# Enclosure_85x58_BHWSL.net
KiCad netlist of a schematic drawn in EAGLE
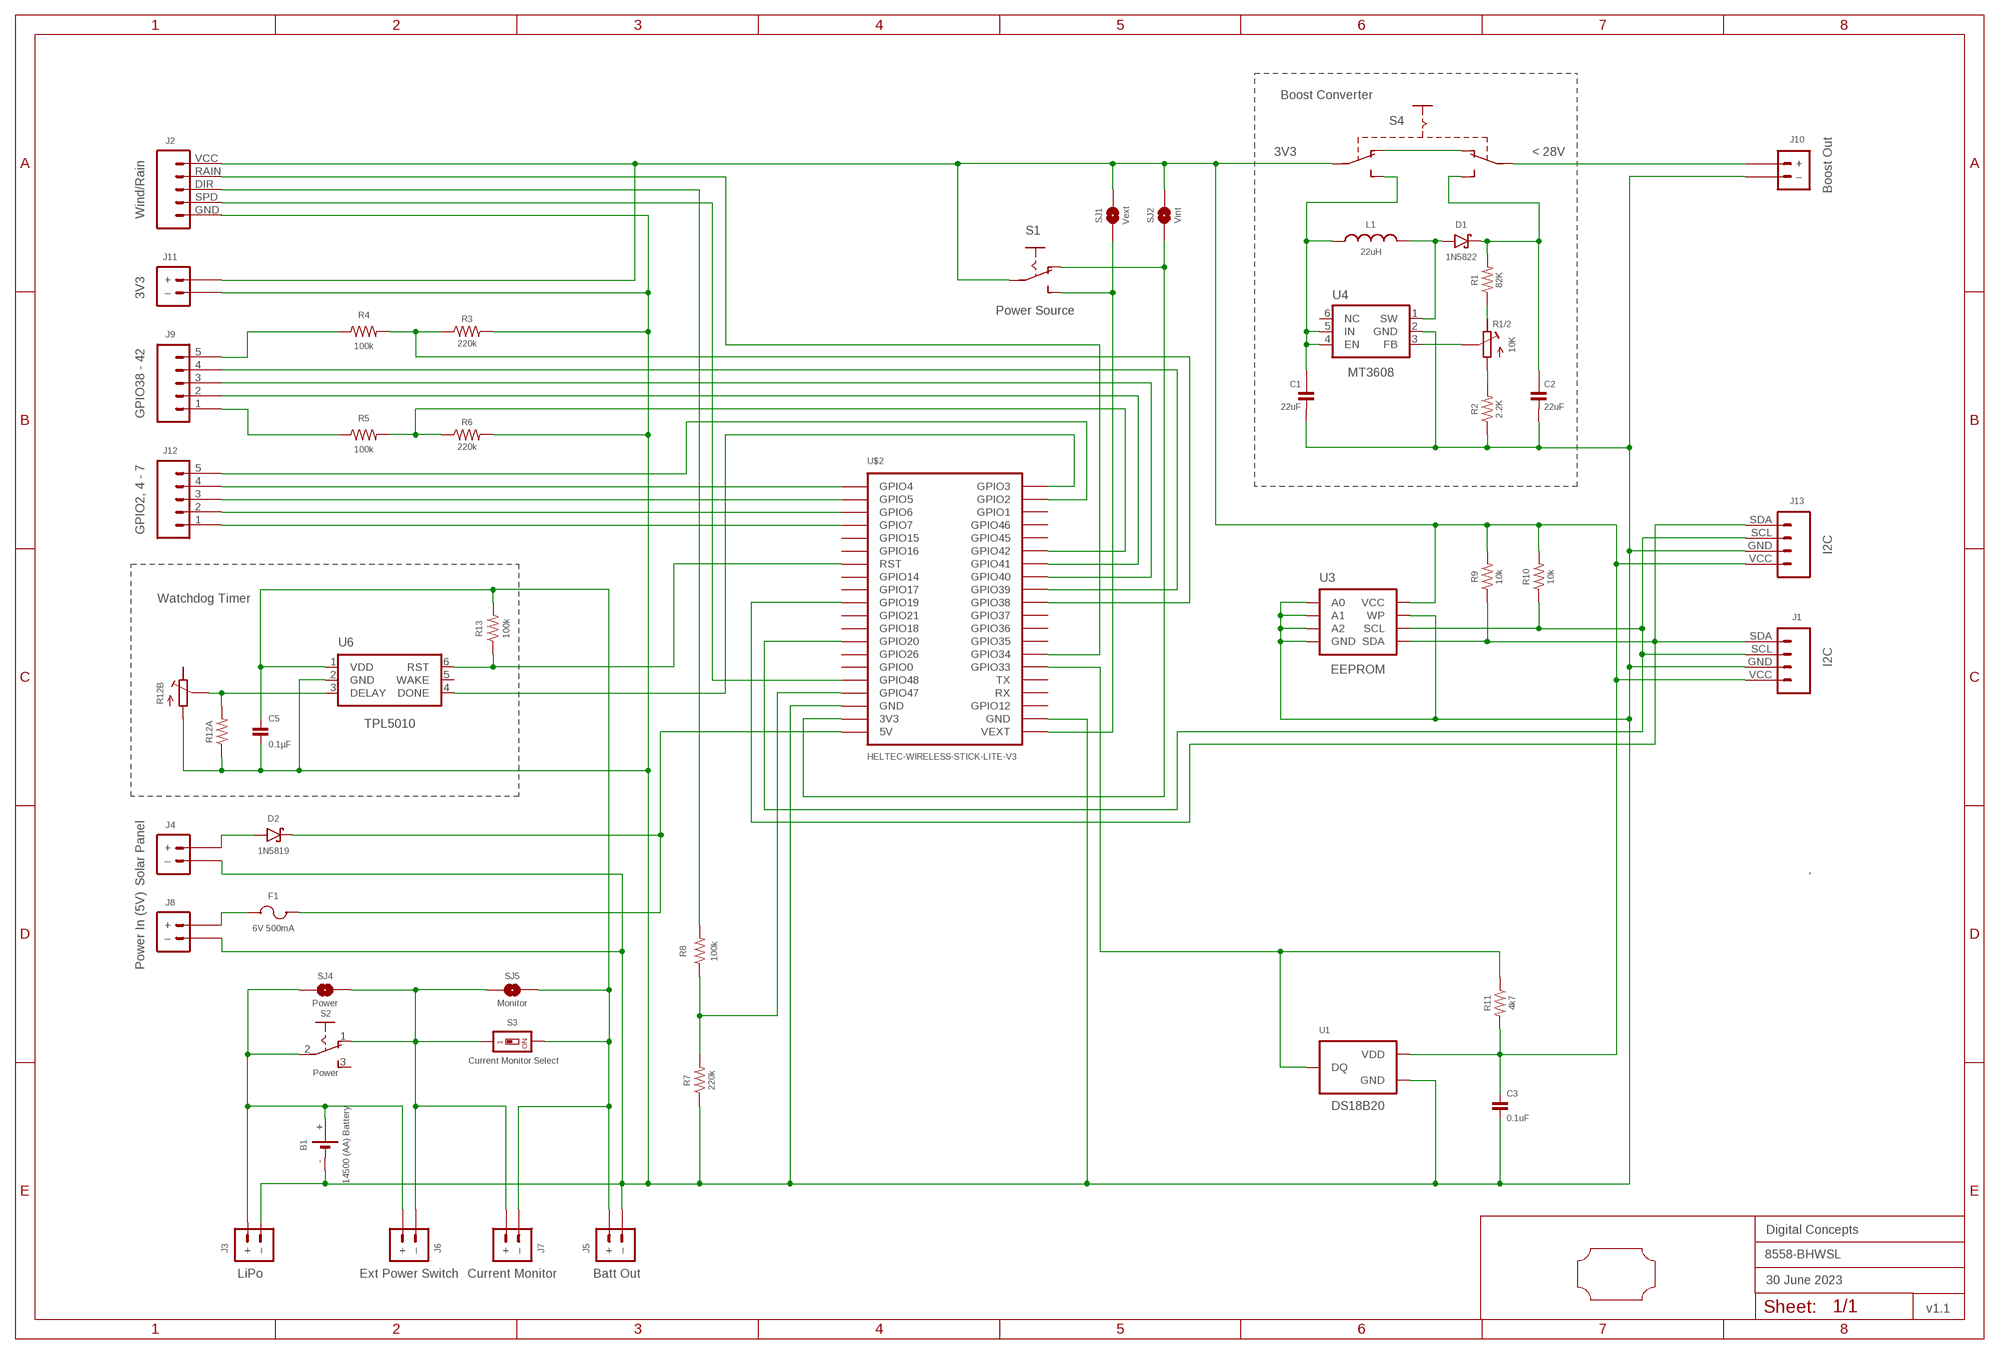
[diagram p0: schematic, sheet 1]

(export (version "E")
  (design (tool "Eeschema 10.0.6"))
  (components
    (comp (ref "B1")
      (value "14500 (AA) Battery")
      (footprint "eagle-import:BATTERY-14500")
      (libsource (lib "eagle-import") (part "BATTERY-HOLDER-14500(AA)"))
    )
    (comp (ref "C1")
      (value "22uF")
      (footprint "eagle-import:C1206")
      (libsource (lib "eagle-import") (part "CAPACITOR-1206"))
    )
    (comp (ref "C2")
      (value "22uF")
      (footprint "eagle-import:C1206")
      (libsource (lib "eagle-import") (part "CAPACITOR-1206"))
    )
    (comp (ref "C3")
      (value "0.1uF")
      (footprint "eagle-import:C0805")
      (libsource (lib "eagle-import") (part "CAPACITOR-0805"))
    )
    (comp (ref "C5")
      (value "0.1µF")
      (footprint "eagle-import:C0805")
      (libsource (lib "eagle-import") (part "CAPACITOR-0805"))
    )
    (comp (ref "D1")
      (value "1N5822")
      (footprint "eagle-import:DIODE_SMB")
      (libsource (lib "eagle-import") (part "DIODE-SCHOTTKY-1N5822"))
    )
    (comp (ref "D2")
      (value "1N5819")
      (footprint "eagle-import:SOD-123")
      (libsource (lib "eagle-import") (part "1N5819-SOD-123"))
    )
    (comp (ref "F1")
      (value "6V 500mA")
      (footprint "eagle-import:F0805")
      (libsource (lib "eagle-import") (part "MF-PSMF050X-2"))
    )
    (comp (ref "J1")
      (value "I2C")
      (footprint "eagle-import:JST-PH2.0-4-VERTICAL-I2C")
      (libsource (lib "eagle-import") (part "JST-PH2.0-4-VERTICAL-I2C"))
    )
    (comp (ref "J2")
      (value "Wind/Rain")
      (footprint "eagle-import:JST-PH2.0-5-WEATHER")
      (libsource (lib "eagle-import") (part "JST-PH2.0-5-VERTICAL-WEATHER"))
    )
    (comp (ref "J3")
      (value "LiPo")
      (footprint "eagle-import:JST-PH2.0-2-HORIZONTAL")
      (libsource (lib "eagle-import") (part "JST-PH2.0-2-MALE-HORIZONTALJST-PTH-2"))
    )
    (comp (ref "J4")
      (value "Solar Panel")
      (footprint "eagle-import:JST-PH2.0-2-VERTICAL-POWER")
      (libsource (lib "eagle-import") (part "JST-PH2.0-2-VERTICAL-POWER"))
    )
    (comp (ref "J5")
      (value "Batt Out")
      (footprint "eagle-import:JST-GH1.25-2-HORIZONTAL")
      (libsource (lib "eagle-import") (part "JST-GH1.25-2-HORIZONTAL-POWER"))
    )
    (comp (ref "J6")
      (value "Ext Power Switch")
      (footprint "eagle-import:JST-PH2.0-2-DUAL-POWER")
      (libsource (lib "eagle-import") (part "JST-PH2.0-2-DUAL-POWERJST-PTH-2"))
    )
    (comp (ref "J7")
      (value "Current Monitor")
      (footprint "eagle-import:JST-PH2.0-2-HORIZONTAL-POWER@1")
      (libsource (lib "eagle-import") (part "JST-PH2.0-2-HORIZONTAL-POWERJST-PTH-2"))
    )
    (comp (ref "J8")
      (value "Power In (5V)")
      (footprint "eagle-import:JST-PH2.0-2-HORIZONTAL-POWER")
      (libsource (lib "eagle-import") (part "JST-PH2.0-2-H-POWER"))
    )
    (comp (ref "J9")
      (value "GPIO38 - 42")
      (footprint "eagle-import:JST-PH2.0-5-HORIZONTAL")
      (libsource (lib "eagle-import") (part "JST-PH2.0-5-HORIZONTAL"))
    )
    (comp (ref "J10")
      (value "Boost Out")
      (footprint "eagle-import:JST-PH2.0-2-HORIZONTAL-POWER")
      (libsource (lib "eagle-import") (part "JST-PH2.0-2-H-POWER"))
    )
    (comp (ref "J11")
      (value "3V3")
      (footprint "eagle-import:JST-PH2.0-2-HORIZONTAL-POWER")
      (libsource (lib "eagle-import") (part "JST-PH2.0-2-H-POWER"))
    )
    (comp (ref "J12")
      (value "GPIO2, 4 - 7")
      (footprint "eagle-import:JST-PH2.0-5-HORIZONTAL")
      (libsource (lib "eagle-import") (part "JST-PH2.0-5-HORIZONTAL"))
    )
    (comp (ref "J13")
      (value "I2C")
      (footprint "eagle-import:JST-PH2.0-4-HORIZONTAL-I2C")
      (libsource (lib "eagle-import") (part "JST-PH2.0-4-HORIZONTAL-I2C"))
    )
    (comp (ref "L1")
      (value "22uH")
      (footprint "eagle-import:CDRH104R+6D28")
      (libsource (lib "eagle-import") (part "INDUCTOR-CDRH104R/6D28L5038P"))
    )
    (comp (ref "R1")
      (value "82K")
      (footprint "eagle-import:R0805")
      (libsource (lib "eagle-import") (part "RESISTORR0805"))
    )
    (comp (ref "R1/2")
      (value "10K")
      (footprint "eagle-import:RTRIM64P")
      (libsource (lib "eagle-import") (part "RESISTOR-TRIMM-BAOTER-HORIZONTAL"))
    )
    (comp (ref "R2")
      (value "2.2K")
      (footprint "eagle-import:R0805")
      (libsource (lib "eagle-import") (part "RESISTORR0805"))
    )
    (comp (ref "R3")
      (value "220k")
      (footprint "eagle-import:R0805")
      (libsource (lib "eagle-import") (part "RESISTORR0805"))
    )
    (comp (ref "R4")
      (value "100k")
      (footprint "eagle-import:R0805")
      (libsource (lib "eagle-import") (part "RESISTORR0805"))
    )
    (comp (ref "R5")
      (value "100k")
      (footprint "eagle-import:R0805")
      (libsource (lib "eagle-import") (part "RESISTORR0805"))
    )
    (comp (ref "R6")
      (value "220k")
      (footprint "eagle-import:R0805")
      (libsource (lib "eagle-import") (part "RESISTORR0805"))
    )
    (comp (ref "R7")
      (value "220k")
      (footprint "eagle-import:R0805")
      (libsource (lib "eagle-import") (part "RESISTORR0805"))
    )
    (comp (ref "R8")
      (value "100k")
      (footprint "eagle-import:R0805")
      (libsource (lib "eagle-import") (part "RESISTORR0805"))
    )
    (comp (ref "R9")
      (value "10k")
      (footprint "eagle-import:R0805")
      (libsource (lib "eagle-import") (part "RESISTORR0805"))
    )
    (comp (ref "R10")
      (value "10k")
      (footprint "eagle-import:R0805")
      (libsource (lib "eagle-import") (part "RESISTORR0805"))
    )
    (comp (ref "R11")
      (value "4k7")
      (footprint "eagle-import:R0805")
      (libsource (lib "eagle-import") (part "RESISTORR0805"))
    )
    (comp (ref "R12A")
      (value "RESISTORR0805")
      (footprint "eagle-import:R0805")
      (libsource (lib "eagle-import") (part "RESISTORR0805"))
    )
    (comp (ref "R12B")
      (value "RESISTOR-TRIMM-33")
      (footprint "eagle-import:RTRIM3_3")
      (libsource (lib "eagle-import") (part "RESISTOR-TRIMM-33"))
    )
    (comp (ref "R13")
      (value "100k")
      (footprint "eagle-import:R0805")
      (libsource (lib "eagle-import") (part "RESISTORR0805"))
    )
    (comp (ref "S1")
      (value "Power Source")
      (footprint "eagle-import:SWITCH-SPDT-SMT")
      (libsource (lib "eagle-import") (part "SWITCH-SLIDE-SPDT-SMT"))
    )
    (comp (ref "S2")
      (value "Power")
      (footprint "eagle-import:SWITCH-SLIDE-SPDT")
      (libsource (lib "eagle-import") (part "SWITCH-SLIDE-SPDT"))
    )
    (comp (ref "S3")
      (value "Current Monitor Select")
      (footprint "eagle-import:SMD-001")
      (libsource (lib "eagle-import") (part "SWITCH-DIP-SWS001"))
    )
    (comp (ref "S4")
      (value "SWITCH-SLIDE-DPDT-PTH-S")
      (footprint "eagle-import:SWITCH-DPDT-PTH")
      (libsource (lib "eagle-import") (part "SWITCH-SLIDE-DPDT-PTH-S"))
    )
    (comp (ref "SJ1")
      (value "Vext")
      (footprint "eagle-import:SJ")
      (libsource (lib "eagle-import") (part "SJ"))
    )
    (comp (ref "SJ2")
      (value "Vint")
      (footprint "eagle-import:SJ-VIA-1")
      (libsource (lib "eagle-import") (part "SJ-V-1"))
    )
    (comp (ref "SJ4")
      (value "Power")
      (footprint "eagle-import:SJ")
      (libsource (lib "eagle-import") (part "SJ"))
    )
    (comp (ref "SJ5")
      (value "Monitor")
      (footprint "eagle-import:SJ")
      (libsource (lib "eagle-import") (part "SJ"))
    )
    (comp (ref "U$1")
      (value "PCB-OUTLINE-85X58")
      (footprint "eagle-import:PROTO-28X18-OUTLINE")
      (libsource (lib "eagle-import") (part "PCB-OUTLINE-85X58"))
    )
    (comp (ref "U$2")
      (value "HELTEC-WIRELESS-STICK-LITE-V3")
      (footprint "eagle-import:HELTEC-WIRELESS-STICK-LITE-V3")
      (libsource (lib "eagle-import") (part "HELTEC-WIRELESS-STICK-LITE-V3"))
    )
    (comp (ref "U1")
      (value "DS18B20")
      (footprint "eagle-import:TO-92")
      (fields (field (name "MF") "Maxim Integrated"))
      (libsource (lib "eagle-import") (part "THERMOMETER-DS18B20"))
    )
    (comp (ref "U3")
      (value "EEPROM")
      (footprint "eagle-import:SOP-8")
      (libsource (lib "eagle-import") (part "AT24CXX-EEPROM"))
    )
    (comp (ref "U4")
      (value "MT3608")
      (footprint "eagle-import:SOT-23-6@1")
      (libsource (lib "eagle-import") (part "MT3608"))
    )
    (comp (ref "U6")
      (value "TPL5010")
      (footprint "eagle-import:SOT-23-6")
      (libsource (lib "eagle-import") (part "TPL5010DDCR"))
    )
  )
  (nets
    (net (code "1") (name "Net-(D2-PadA)") (class "Default")
      (node (ref "D2") (pin "A") (pinfunction "A_A") (pintype "passive"))
      (node (ref "J4") (pin "+") (pinfunction "+_+") (pintype "power_in"))
    )
    (net (code "2") (name "Net-(D2-PadC)") (class "Default")
      (node (ref "D2") (pin "C") (pinfunction "C_C") (pintype "passive"))
      (node (ref "F1") (pin "2") (pinfunction "2_2") (pintype "passive"))
      (node (ref "U$2") (pin "5V") (pinfunction "5V_5V") (pintype "bidirectional"))
    )
    (net (code "3") (name "Net-(F1-Pad1)") (class "Default")
      (node (ref "F1") (pin "1") (pinfunction "1_1") (pintype "passive"))
      (node (ref "J8") (pin "+") (pinfunction "+_+") (pintype "power_in"))
    )
    (net (code "4") (name "Net-(J1-1)") (class "Default")
      (node (ref "J1") (pin "SDA") (pinfunction "1_SDA") (pintype "passive"))
      (node (ref "J13") (pin "SDA") (pinfunction "1_SDA") (pintype "passive"))
      (node (ref "R9") (pin "1") (pinfunction "1_1") (pintype "passive"))
      (node (ref "U$2") (pin "GPIO19") (pinfunction "GPIO19_GPIO19") (pintype "bidirectional"))
      (node (ref "U3") (pin "P$5") (pinfunction "SDA_P$5") (pintype "bidirectional"))
    )
    (net (code "5") (name "Net-(J1-2)") (class "Default")
      (node (ref "J1") (pin "SCL") (pinfunction "2_SCL") (pintype "passive"))
      (node (ref "J13") (pin "SCL") (pinfunction "2_SCL") (pintype "passive"))
      (node (ref "R10") (pin "1") (pinfunction "1_1") (pintype "passive"))
      (node (ref "U$2") (pin "GPIO20") (pinfunction "GPIO20_GPIO20") (pintype "bidirectional"))
      (node (ref "U3") (pin "P$6") (pinfunction "SCL_P$6") (pintype "bidirectional"))
    )
    (net (code "6") (name "Net-(J1-3)") (class "Default")
      (node (ref "B1") (pin "-") (pinfunction "-_-") (pintype "power_in"))
      (node (ref "C1") (pin "2") (pinfunction "2_2") (pintype "passive"))
      (node (ref "C2") (pin "2") (pinfunction "2_2") (pintype "passive"))
      (node (ref "C3") (pin "2") (pinfunction "2_2") (pintype "passive"))
      (node (ref "C5") (pin "2") (pinfunction "2_2") (pintype "passive"))
      (node (ref "J1") (pin "GND") (pinfunction "3_GND") (pintype "passive"))
      (node (ref "J10") (pin "-") (pinfunction "–_-") (pintype "power_in"))
      (node (ref "J11") (pin "-") (pinfunction "–_-") (pintype "power_in"))
      (node (ref "J13") (pin "GND") (pinfunction "3_GND") (pintype "passive"))
      (node (ref "J2") (pin "GND") (pinfunction "5_GND") (pintype "passive"))
      (node (ref "J3") (pin "-") (pinfunction "–_-") (pintype "power_in"))
      (node (ref "J4") (pin "-") (pinfunction "–_-") (pintype "power_in"))
      (node (ref "J5") (pin "-") (pinfunction "–_-") (pintype "power_in"))
      (node (ref "J8") (pin "-") (pinfunction "–_-") (pintype "power_in"))
      (node (ref "R12A") (pin "1") (pinfunction "1_1") (pintype "passive"))
      (node (ref "R12B") (pin "1") (pinfunction "A_1") (pintype "passive"))
      (node (ref "R2") (pin "1") (pinfunction "1_1") (pintype "passive"))
      (node (ref "R3") (pin "2") (pinfunction "2_2") (pintype "passive"))
      (node (ref "R6") (pin "2") (pinfunction "2_2") (pintype "passive"))
      (node (ref "R7") (pin "1") (pinfunction "1_1") (pintype "passive"))
      (node (ref "U$2") (pin "GND@18") (pinfunction "GND_GND@18") (pintype "bidirectional"))
      (node (ref "U$2") (pin "GND@22") (pinfunction "GND_GND@22") (pintype "bidirectional"))
      (node (ref "U1") (pin "1") (pinfunction "GND_1") (pintype "power_in"))
      (node (ref "U3") (pin "P$1") (pinfunction "A0_P$1") (pintype "bidirectional"))
      (node (ref "U3") (pin "P$2") (pinfunction "A1_P$2") (pintype "bidirectional"))
      (node (ref "U3") (pin "P$3") (pinfunction "A2_P$3") (pintype "bidirectional"))
      (node (ref "U3") (pin "P$4") (pinfunction "GND_P$4") (pintype "bidirectional"))
      (node (ref "U3") (pin "P$7") (pinfunction "WP_P$7") (pintype "bidirectional"))
      (node (ref "U4") (pin "2") (pinfunction "GND_2") (pintype "power_in"))
      (node (ref "U6") (pin "2") (pinfunction "GND_2") (pintype "power_in"))
    )
    (net (code "7") (name "Net-(J1-4)") (class "Default")
      (node (ref "C3") (pin "1") (pinfunction "1_1") (pintype "passive"))
      (node (ref "J1") (pin "VCC") (pinfunction "4_VCC") (pintype "passive"))
      (node (ref "J11") (pin "+") (pinfunction "+_+") (pintype "power_in"))
      (node (ref "J13") (pin "VCC") (pinfunction "4_VCC") (pintype "passive"))
      (node (ref "J2") (pin "VCC") (pinfunction "1_VCC") (pintype "passive"))
      (node (ref "R10") (pin "2") (pinfunction "2_2") (pintype "passive"))
      (node (ref "R11") (pin "2") (pinfunction "2_2") (pintype "passive"))
      (node (ref "R9") (pin "2") (pinfunction "2_2") (pintype "passive"))
      (node (ref "S1") (pin "COMMON") (pinfunction "P_COMMON") (pintype "passive"))
      (node (ref "S4") (pin "P$5") (pinfunction "P2_P$5") (pintype "passive"))
      (node (ref "SJ1") (pin "1") (pinfunction "1_1") (pintype "passive"))
      (node (ref "SJ2") (pin "1") (pinfunction "1_1") (pintype "passive"))
      (node (ref "SJ2") (pin "1@V") (pinfunction "1_1@V") (pintype "passive"))
      (node (ref "U1") (pin "3") (pinfunction "VDD_3") (pintype "power_in"))
      (node (ref "U3") (pin "P$8") (pinfunction "VCC_P$8") (pintype "bidirectional"))
    )
    (net (code "8") (name "Net-(J2-2)") (class "Default")
      (node (ref "J2") (pin "RAIN") (pinfunction "2_RAIN") (pintype "passive"))
      (node (ref "U$2") (pin "GPIO34") (pinfunction "GPIO34_GPIO34") (pintype "bidirectional"))
    )
    (net (code "9") (name "Net-(J2-3)") (class "Default")
      (node (ref "J2") (pin "DIR") (pinfunction "3_DIR") (pintype "passive"))
      (node (ref "R8") (pin "2") (pinfunction "2_2") (pintype "passive"))
    )
    (net (code "10") (name "Net-(J2-4)") (class "Default")
      (node (ref "J2") (pin "SPD") (pinfunction "4_SPD") (pintype "passive"))
      (node (ref "U$2") (pin "GPIO48") (pinfunction "GPIO48_GPIO48") (pintype "bidirectional"))
    )
    (net (code "11") (name "Net-(J6-–)") (class "Default")
      (node (ref "J6") (pin "-") (pinfunction "–_-") (pintype "power_in"))
      (node (ref "J7") (pin "+") (pinfunction "+_+") (pintype "power_in"))
      (node (ref "S2") (pin "1") (pinfunction "O_1") (pintype "passive"))
      (node (ref "S3") (pin "1") (pinfunction "1_1") (pintype "passive"))
      (node (ref "SJ4") (pin "1") (pinfunction "1_1") (pintype "passive"))
      (node (ref "SJ5") (pin "2") (pinfunction "2_2") (pintype "passive"))
    )
    (net (code "12") (name "Net-(J7-–)") (class "Default")
      (node (ref "C5") (pin "1") (pinfunction "1_1") (pintype "passive"))
      (node (ref "J5") (pin "+") (pinfunction "+_+") (pintype "power_in"))
      (node (ref "J7") (pin "-") (pinfunction "–_-") (pintype "power_in"))
      (node (ref "R13") (pin "2") (pinfunction "2_2") (pintype "passive"))
      (node (ref "S3") (pin "2") (pinfunction "2_2") (pintype "passive"))
      (node (ref "SJ5") (pin "1") (pinfunction "1_1") (pintype "passive"))
      (node (ref "U6") (pin "1") (pinfunction "VDD_1") (pintype "power_in"))
    )
    (net (code "13") (name "Net-(J9-Pad1)") (class "Default")
      (node (ref "J9") (pin "1") (pinfunction "1_1") (pintype "passive"))
      (node (ref "R5") (pin "1") (pinfunction "1_1") (pintype "passive"))
    )
    (net (code "14") (name "Net-(J9-Pad2)") (class "Default")
      (node (ref "J9") (pin "2") (pinfunction "2_2") (pintype "passive"))
      (node (ref "U$2") (pin "GPIO41") (pinfunction "GPIO41_GPIO41") (pintype "bidirectional"))
    )
    (net (code "15") (name "Net-(J9-Pad3)") (class "Default")
      (node (ref "J9") (pin "3") (pinfunction "3_3") (pintype "passive"))
      (node (ref "U$2") (pin "GPIO40") (pinfunction "GPIO40_GPIO40") (pintype "bidirectional"))
    )
    (net (code "16") (name "Net-(J9-Pad4)") (class "Default")
      (node (ref "J9") (pin "4") (pinfunction "4_4") (pintype "passive"))
      (node (ref "U$2") (pin "GPIO39") (pinfunction "GPIO39_GPIO39") (pintype "bidirectional"))
    )
    (net (code "17") (name "Net-(J9-Pad5)") (class "Default")
      (node (ref "J9") (pin "5") (pinfunction "5_5") (pintype "passive"))
      (node (ref "R4") (pin "1") (pinfunction "1_1") (pintype "passive"))
    )
    (net (code "18") (name "Net-(J12-Pad1)") (class "Default")
      (node (ref "J12") (pin "1") (pinfunction "1_1") (pintype "passive"))
      (node (ref "U$2") (pin "GPIO7") (pinfunction "GPIO7_GPIO7") (pintype "bidirectional"))
    )
    (net (code "19") (name "Net-(J12-Pad2)") (class "Default")
      (node (ref "J12") (pin "2") (pinfunction "2_2") (pintype "passive"))
      (node (ref "U$2") (pin "GPIO6") (pinfunction "GPIO6_GPIO6") (pintype "bidirectional"))
    )
    (net (code "20") (name "Net-(J12-Pad3)") (class "Default")
      (node (ref "J12") (pin "3") (pinfunction "3_3") (pintype "passive"))
      (node (ref "U$2") (pin "GPIO5") (pinfunction "GPIO5_GPIO5") (pintype "bidirectional"))
    )
    (net (code "21") (name "Net-(J12-Pad4)") (class "Default")
      (node (ref "J12") (pin "4") (pinfunction "4_4") (pintype "passive"))
      (node (ref "U$2") (pin "GPIO4") (pinfunction "GPIO4_GPIO4") (pintype "bidirectional"))
    )
    (net (code "22") (name "Net-(J12-Pad5)") (class "Default")
      (node (ref "J12") (pin "5") (pinfunction "5_5") (pintype "passive"))
      (node (ref "U$2") (pin "GPIO2") (pinfunction "GPIO2_GPIO2") (pintype "bidirectional"))
    )
    (net (code "23") (name "Net-(R1/2-A)") (class "Default")
      (node (ref "R1/2") (pin "1") (pinfunction "A_1") (pintype "passive"))
      (node (ref "R2") (pin "2") (pinfunction "2_2") (pintype "passive"))
    )
    (net (code "24") (name "Net-(R1/2-E)") (class "Default")
      (node (ref "R1") (pin "1") (pinfunction "1_1") (pintype "passive"))
      (node (ref "R1/2") (pin "3") (pinfunction "E_3") (pintype "passive"))
    )
    (net (code "25") (name "Net-(R1/2-S)") (class "Default")
      (node (ref "R1/2") (pin "2") (pinfunction "S_2") (pintype "passive"))
      (node (ref "U4") (pin "3") (pinfunction "FB_3") (pintype "input"))
    )
    (net (code "26") (name "Net-(R3-Pad1)") (class "Default")
      (node (ref "R3") (pin "1") (pinfunction "1_1") (pintype "passive"))
      (node (ref "R4") (pin "2") (pinfunction "2_2") (pintype "passive"))
      (node (ref "U$2") (pin "GPIO38") (pinfunction "GPIO38_GPIO38") (pintype "bidirectional"))
    )
    (net (code "27") (name "Net-(R5-Pad2)") (class "Default")
      (node (ref "R5") (pin "2") (pinfunction "2_2") (pintype "passive"))
      (node (ref "R6") (pin "1") (pinfunction "1_1") (pintype "passive"))
      (node (ref "U$2") (pin "GPIO42") (pinfunction "GPIO42_GPIO42") (pintype "bidirectional"))
    )
    (net (code "28") (name "Net-(R7-Pad2)") (class "Default")
      (node (ref "R7") (pin "2") (pinfunction "2_2") (pintype "passive"))
      (node (ref "R8") (pin "1") (pinfunction "1_1") (pintype "passive"))
      (node (ref "U$2") (pin "GPIO47") (pinfunction "GPIO47_GPIO47") (pintype "bidirectional"))
    )
    (net (code "29") (name "Net-(R12B-S)") (class "Default")
      (node (ref "R12A") (pin "2") (pinfunction "2_2") (pintype "passive"))
      (node (ref "R12B") (pin "2") (pinfunction "S_2") (pintype "passive"))
      (node (ref "U6") (pin "3") (pinfunction "DELAY_3") (pintype "input"))
    )
    (net (code "30") (name "Net-(S1-O)") (class "Default")
      (node (ref "S1") (pin "P$1") (pinfunction "O_P$1") (pintype "passive"))
      (node (ref "SJ2") (pin "2") (pinfunction "2_2") (pintype "passive"))
      (node (ref "U$2") (pin "3V3") (pinfunction "3V3_3V3") (pintype "bidirectional"))
    )
    (net (code "31") (name "Net-(S1-S)") (class "Default")
      (node (ref "S1") (pin "P$2") (pinfunction "S_P$2") (pintype "passive"))
      (node (ref "SJ1") (pin "2") (pinfunction "2_2") (pintype "passive"))
      (node (ref "U$2") (pin "VEXT") (pinfunction "VEXT_VEXT") (pintype "bidirectional"))
    )
    (net (code "32") (name "Net-(S2-P)") (class "Default")
      (node (ref "B1") (pin "+") (pinfunction "+_+") (pintype "power_in"))
      (node (ref "J3") (pin "+") (pinfunction "+_+") (pintype "power_in"))
      (node (ref "J6") (pin "+") (pinfunction "+_+") (pintype "power_in"))
      (node (ref "S2") (pin "2") (pinfunction "P_2") (pintype "passive"))
      (node (ref "SJ4") (pin "2") (pinfunction "2_2") (pintype "passive"))
    )
    (net (code "33") (name "Net-(S4-O1)") (class "Default")
      (node (ref "S4") (pin "P$1") (pinfunction "O1_P$1") (pintype "passive"))
      (node (ref "S4") (pin "P$4") (pinfunction "O2_P$4") (pintype "passive"))
    )
    (net (code "34") (name "Net-(S4-P1)") (class "Default")
      (node (ref "J10") (pin "+") (pinfunction "+_+") (pintype "power_in"))
      (node (ref "S4") (pin "P$2") (pinfunction "P1_P$2") (pintype "passive"))
    )
    (net (code "35") (name "Net-(S4-S1)") (class "Default")
      (node (ref "C2") (pin "1") (pinfunction "1_1") (pintype "passive"))
      (node (ref "D1") (pin "C") (pinfunction "C_C") (pintype "passive"))
      (node (ref "R1") (pin "2") (pinfunction "2_2") (pintype "passive"))
      (node (ref "S4") (pin "P$3") (pinfunction "S1_P$3") (pintype "passive"))
    )
    (net (code "36") (name "Net-(S4-S2)") (class "Default")
      (node (ref "C1") (pin "1") (pinfunction "1_1") (pintype "passive"))
      (node (ref "L1") (pin "2") (pinfunction "2_2") (pintype "passive"))
      (node (ref "S4") (pin "P$6") (pinfunction "S2_P$6") (pintype "passive"))
      (node (ref "U4") (pin "4") (pinfunction "EN_4") (pintype "input"))
      (node (ref "U4") (pin "5") (pinfunction "IN_5") (pintype "power_in"))
    )
    (net (code "37") (name "Net-(U1-DQ)") (class "Default")
      (node (ref "R11") (pin "1") (pinfunction "1_1") (pintype "passive"))
      (node (ref "U$2") (pin "GPIO33") (pinfunction "GPIO33_GPIO33") (pintype "bidirectional"))
      (node (ref "U1") (pin "2") (pinfunction "DQ_2") (pintype "bidirectional"))
    )
    (net (code "38") (name "Net-(U4-SW)") (class "Default")
      (node (ref "D1") (pin "A") (pinfunction "A_A") (pintype "passive"))
      (node (ref "L1") (pin "1") (pinfunction "1_1") (pintype "passive"))
      (node (ref "U4") (pin "1") (pinfunction "SW_1") (pintype "power_in"))
    )
    (net (code "39") (name "Net-(U6-DONE)") (class "Default")
      (node (ref "U$2") (pin "GPIO3") (pinfunction "GPIO3_GPIO3") (pintype "bidirectional"))
      (node (ref "U6") (pin "4") (pinfunction "DONE_4") (pintype "input"))
    )
    (net (code "40") (name "Net-(U6-RST)") (class "Default")
      (node (ref "R13") (pin "1") (pinfunction "1_1") (pintype "passive"))
      (node (ref "U$2") (pin "RST") (pinfunction "RST_RST") (pintype "bidirectional"))
      (node (ref "U6") (pin "6") (pinfunction "RST_6") (pintype "output"))
    )
    (net (code "41") (name "unconnected-(R12B-E-Pad3)") (class "Default")
      (node (ref "R12B") (pin "3") (pinfunction "E_3") (pintype "passive"))
    )
    (net (code "42") (name "unconnected-(S2-S-Pad3)") (class "Default")
      (node (ref "S2") (pin "3") (pinfunction "S_3") (pintype "passive"))
    )
    (net (code "43") (name "unconnected-(U$2-PadGPIO0)") (class "Default")
      (node (ref "U$2") (pin "GPIO0") (pinfunction "GPIO0_GPIO0") (pintype "bidirectional"))
    )
    (net (code "44") (name "unconnected-(U$2-PadGPIO1)") (class "Default")
      (node (ref "U$2") (pin "GPIO1") (pinfunction "GPIO1_GPIO1") (pintype "bidirectional"))
    )
    (net (code "45") (name "unconnected-(U$2-PadGPIO12)") (class "Default")
      (node (ref "U$2") (pin "GPIO12") (pinfunction "GPIO12_GPIO12") (pintype "bidirectional"))
    )
    (net (code "46") (name "unconnected-(U$2-PadGPIO14)") (class "Default")
      (node (ref "U$2") (pin "GPIO14") (pinfunction "GPIO14_GPIO14") (pintype "bidirectional"))
    )
    (net (code "47") (name "unconnected-(U$2-PadGPIO15)") (class "Default")
      (node (ref "U$2") (pin "GPIO15") (pinfunction "GPIO15_GPIO15") (pintype "bidirectional"))
    )
    (net (code "48") (name "unconnected-(U$2-PadGPIO16)") (class "Default")
      (node (ref "U$2") (pin "GPIO16") (pinfunction "GPIO16_GPIO16") (pintype "bidirectional"))
    )
    (net (code "49") (name "unconnected-(U$2-PadGPIO17)") (class "Default")
      (node (ref "U$2") (pin "GPIO17") (pinfunction "GPIO17_GPIO17") (pintype "bidirectional"))
    )
    (net (code "50") (name "unconnected-(U$2-PadGPIO18)") (class "Default")
      (node (ref "U$2") (pin "GPIO18") (pinfunction "GPIO18_GPIO18") (pintype "bidirectional"))
    )
    (net (code "51") (name "unconnected-(U$2-PadGPIO21)") (class "Default")
      (node (ref "U$2") (pin "GPIO21") (pinfunction "GPIO21_GPIO21") (pintype "bidirectional"))
    )
    (net (code "52") (name "unconnected-(U$2-PadGPIO26)") (class "Default")
      (node (ref "U$2") (pin "GPIO26") (pinfunction "GPIO26_GPIO26") (pintype "bidirectional"))
    )
    (net (code "53") (name "unconnected-(U$2-PadGPIO35)") (class "Default")
      (node (ref "U$2") (pin "GPIO35") (pinfunction "GPIO35_GPIO35") (pintype "bidirectional"))
    )
    (net (code "54") (name "unconnected-(U$2-PadGPIO36)") (class "Default")
      (node (ref "U$2") (pin "GPIO36") (pinfunction "GPIO36_GPIO36") (pintype "bidirectional"))
    )
    (net (code "55") (name "unconnected-(U$2-PadGPIO37)") (class "Default")
      (node (ref "U$2") (pin "GPIO37") (pinfunction "GPIO37_GPIO37") (pintype "bidirectional"))
    )
    (net (code "56") (name "unconnected-(U$2-PadGPIO45)") (class "Default")
      (node (ref "U$2") (pin "GPIO45") (pinfunction "GPIO45_GPIO45") (pintype "bidirectional"))
    )
    (net (code "57") (name "unconnected-(U$2-PadGPIO46)") (class "Default")
      (node (ref "U$2") (pin "GPIO46") (pinfunction "GPIO46_GPIO46") (pintype "bidirectional"))
    )
    (net (code "58") (name "unconnected-(U$2-PadRX)") (class "Default")
      (node (ref "U$2") (pin "RX") (pinfunction "RX_RX") (pintype "bidirectional"))
    )
    (net (code "59") (name "unconnected-(U$2-PadTX)") (class "Default")
      (node (ref "U$2") (pin "TX") (pinfunction "TX_TX") (pintype "bidirectional"))
    )
    (net (code "60") (name "unconnected-(U4-NC-Pad6)") (class "Default")
      (node (ref "U4") (pin "6") (pinfunction "NC_6") (pintype "no_connect"))
    )
    (net (code "61") (name "unconnected-(U6-WAKE-Pad5)") (class "Default")
      (node (ref "U6") (pin "5") (pinfunction "WAKE_5") (pintype "output"))
    )
  )
)
